# circuit1_ver1.net
KiCad netlist of a schematic drawn in Altium Designer
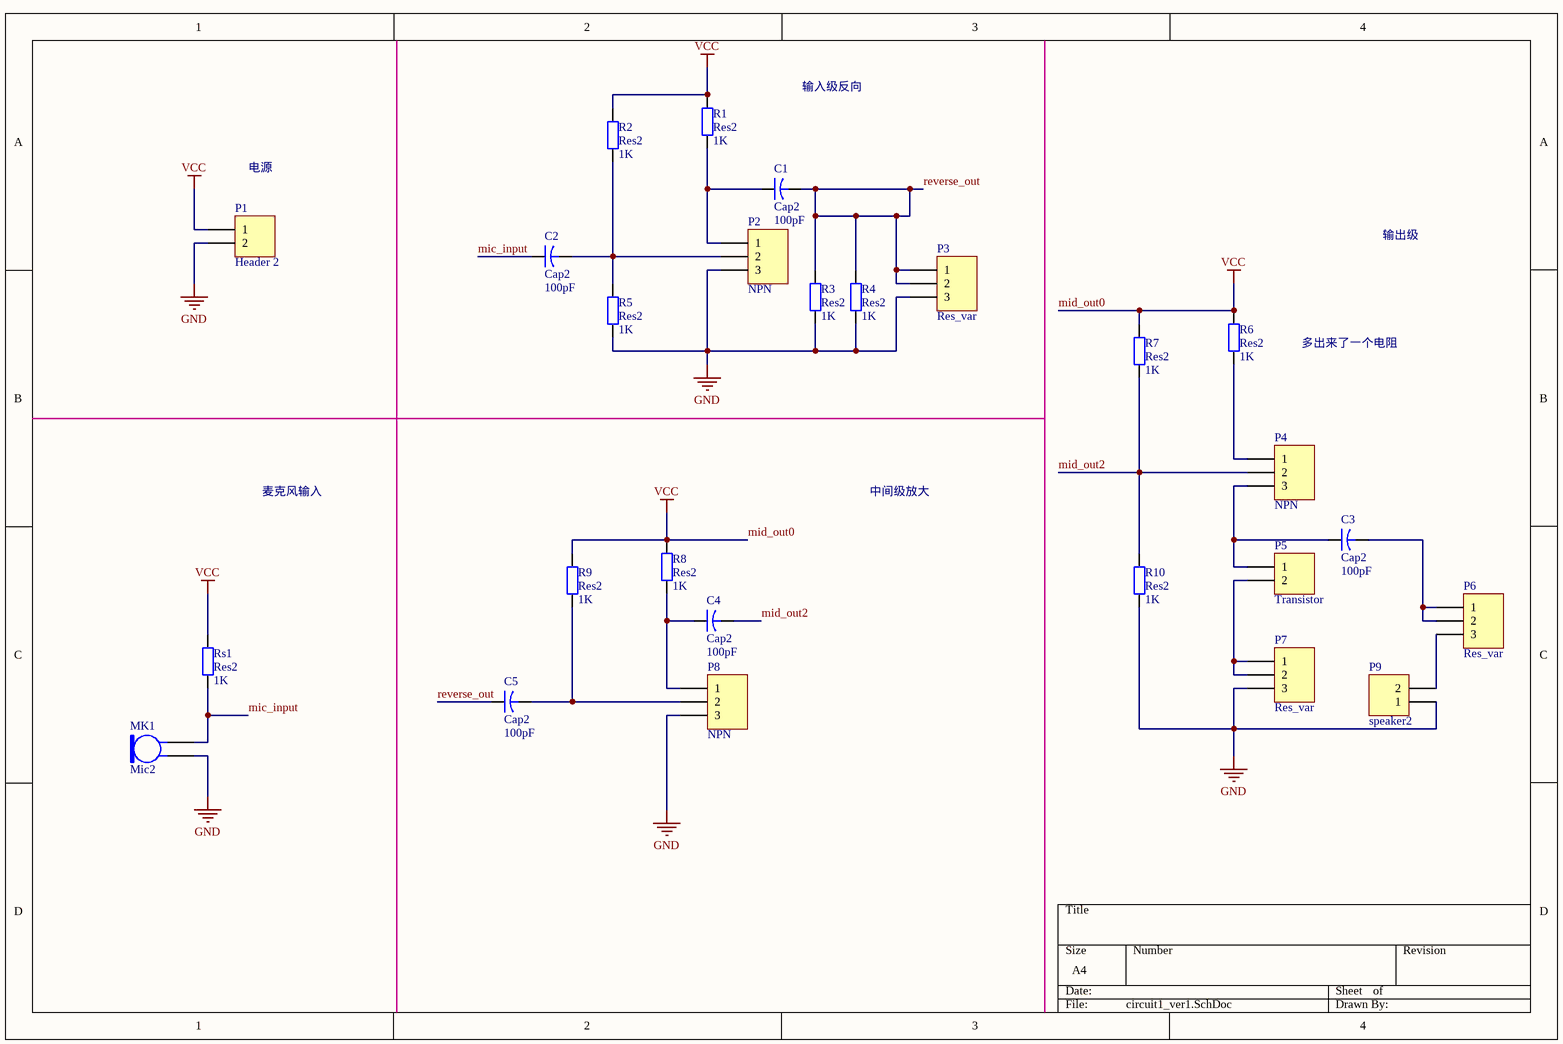
[diagram p0: circuit1_ver1.SchDoc]

(export (version "E")
  (design (tool "Eeschema 10.0.6"))
  (components
    (comp (ref "C1")
      (value "Cap2")
      (footprint "CAPR5-4X5")
      (description "Capacitor")
      (fields (field (name "ALTIUM_VALUE") "100pF") (field (name "PUBLISHER") "Altium Limited"))
      (libsource (lib "Miscellaneous Devices") (part "Cap2"))
    )
    (comp (ref "C2")
      (value "Cap2")
      (footprint "CAPR5-4X5")
      (description "Capacitor")
      (fields (field (name "ALTIUM_VALUE") "100pF") (field (name "PUBLISHER") "Altium Limited"))
      (libsource (lib "Miscellaneous Devices") (part "Cap2"))
    )
    (comp (ref "C3")
      (value "Cap2")
      (footprint "CAPR5-4X5")
      (description "Capacitor")
      (fields (field (name "ALTIUM_VALUE") "100pF") (field (name "PUBLISHER") "Altium Limited"))
      (libsource (lib "Miscellaneous Devices") (part "Cap2"))
    )
    (comp (ref "C4")
      (value "Cap2")
      (footprint "CAPR5-4X5")
      (description "Capacitor")
      (fields (field (name "ALTIUM_VALUE") "100pF") (field (name "PUBLISHER") "Altium Limited"))
      (libsource (lib "Miscellaneous Devices") (part "Cap2"))
    )
    (comp (ref "C5")
      (value "Cap2")
      (footprint "CAPR5-4X5")
      (description "Capacitor")
      (fields (field (name "ALTIUM_VALUE") "100pF") (field (name "PUBLISHER") "Altium Limited"))
      (libsource (lib "Miscellaneous Devices") (part "Cap2"))
    )
    (comp (ref "MK1")
      (value "Mic2")
      (footprint "PIN2")
      (description "Microphone")
      (fields (field (name "PUBLISHER") "Altium Limited"))
      (libsource (lib "Miscellaneous Devices") (part "Mic2"))
    )
    (comp (ref "P1")
      (value "Header 2")
      (footprint "HDR1X2")
      (description "Header, 2-Pin")
      (fields (field (name "PUBLISHER") "Altium Limited"))
      (libsource (lib "Miscellaneous Connectors") (part "Header 2"))
    )
    (comp (ref "P2")
      (value "NPN")
      (footprint "HDR1X3")
      (description "Header, 3-Pin")
      (fields (field (name "PUBLISHER") "Altium Limited"))
      (libsource (lib "Miscellaneous Connectors") (part "Header 3"))
    )
    (comp (ref "P3")
      (value "Res_var")
      (footprint "HDR1X3")
      (description "Header, 3-Pin")
      (fields (field (name "PUBLISHER") "Altium Limited"))
      (libsource (lib "Miscellaneous Connectors") (part "Header 3"))
    )
    (comp (ref "P4")
      (value "NPN")
      (footprint "HDR1X3")
      (description "Header, 3-Pin")
      (fields (field (name "PUBLISHER") "Altium Limited"))
      (libsource (lib "Miscellaneous Connectors") (part "Header 3"))
    )
    (comp (ref "P5")
      (value "Transistor")
      (footprint "HDR1X2")
      (description "Header, 2-Pin")
      (fields (field (name "PUBLISHER") "Altium Limited"))
      (libsource (lib "Miscellaneous Connectors") (part "Header 2"))
    )
    (comp (ref "P6")
      (value "Res_var")
      (footprint "HDR1X3")
      (description "Header, 3-Pin")
      (fields (field (name "PUBLISHER") "Altium Limited"))
      (libsource (lib "Miscellaneous Connectors") (part "Header 3"))
    )
    (comp (ref "P7")
      (value "Res_var")
      (footprint "HDR1X3")
      (description "Header, 3-Pin")
      (fields (field (name "PUBLISHER") "Altium Limited"))
      (libsource (lib "Miscellaneous Connectors") (part "Header 3"))
    )
    (comp (ref "P8")
      (value "NPN")
      (footprint "HDR1X3")
      (description "Header, 3-Pin")
      (fields (field (name "PUBLISHER") "Altium Limited"))
      (libsource (lib "Miscellaneous Connectors") (part "Header 3"))
    )
    (comp (ref "P9")
      (value "speaker2")
      (footprint "HDR1X2")
      (description "Header, 2-Pin")
      (fields (field (name "PUBLISHER") "Altium Limited"))
      (libsource (lib "") (part "Header 2_1"))
    )
    (comp (ref "R1")
      (value "Res2")
      (footprint "AXIAL-0.4")
      (description "Resistor")
      (fields (field (name "ALTIUM_VALUE") "1K") (field (name "PUBLISHER") "Altium Limited"))
      (libsource (lib "Miscellaneous Devices") (part "Res2"))
    )
    (comp (ref "R2")
      (value "Res2")
      (footprint "AXIAL-0.4")
      (description "Resistor")
      (fields (field (name "ALTIUM_VALUE") "1K") (field (name "PUBLISHER") "Altium Limited"))
      (libsource (lib "Miscellaneous Devices") (part "Res2"))
    )
    (comp (ref "R3")
      (value "Res2")
      (footprint "AXIAL-0.4")
      (description "Resistor")
      (fields (field (name "ALTIUM_VALUE") "1K") (field (name "PUBLISHER") "Altium Limited"))
      (libsource (lib "Miscellaneous Devices") (part "Res2"))
    )
    (comp (ref "R4")
      (value "Res2")
      (footprint "AXIAL-0.4")
      (description "Resistor")
      (fields (field (name "ALTIUM_VALUE") "1K") (field (name "PUBLISHER") "Altium Limited"))
      (libsource (lib "Miscellaneous Devices") (part "Res2"))
    )
    (comp (ref "R5")
      (value "Res2")
      (footprint "AXIAL-0.4")
      (description "Resistor")
      (fields (field (name "ALTIUM_VALUE") "1K") (field (name "PUBLISHER") "Altium Limited"))
      (libsource (lib "Miscellaneous Devices") (part "Res2"))
    )
    (comp (ref "R6")
      (value "Res2")
      (footprint "AXIAL-0.4")
      (description "Resistor")
      (fields (field (name "ALTIUM_VALUE") "1K") (field (name "PUBLISHER") "Altium Limited"))
      (libsource (lib "Miscellaneous Devices") (part "Res2"))
    )
    (comp (ref "R7")
      (value "Res2")
      (footprint "AXIAL-0.4")
      (description "Resistor")
      (fields (field (name "ALTIUM_VALUE") "1K") (field (name "PUBLISHER") "Altium Limited"))
      (libsource (lib "Miscellaneous Devices") (part "Res2"))
    )
    (comp (ref "R8")
      (value "Res2")
      (footprint "AXIAL-0.4")
      (description "Resistor")
      (fields (field (name "ALTIUM_VALUE") "1K") (field (name "PUBLISHER") "Altium Limited"))
      (libsource (lib "Miscellaneous Devices") (part "Res2"))
    )
    (comp (ref "R9")
      (value "Res2")
      (footprint "AXIAL-0.4")
      (description "Resistor")
      (fields (field (name "ALTIUM_VALUE") "1K") (field (name "PUBLISHER") "Altium Limited"))
      (libsource (lib "Miscellaneous Devices") (part "Res2"))
    )
    (comp (ref "R10")
      (value "Res2")
      (footprint "AXIAL-0.4")
      (description "Resistor")
      (fields (field (name "ALTIUM_VALUE") "1K") (field (name "PUBLISHER") "Altium Limited"))
      (libsource (lib "Miscellaneous Devices") (part "Res2"))
    )
    (comp (ref "Rs1")
      (value "Res2")
      (footprint "AXIAL-0.4")
      (description "Resistor")
      (fields (field (name "ALTIUM_VALUE") "1K") (field (name "PUBLISHER") "Altium Limited"))
      (libsource (lib "Miscellaneous Devices") (part "Res2"))
    )
  )
  (nets
    (net (code "1") (name "/mic_input") (class "Default")
      (node (ref "C2") (pin "1") (pinfunction "1_1") (pintype "passive"))
      (node (ref "MK1") (pin "2") (pinfunction "2_2") (pintype "passive"))
      (node (ref "Rs1") (pin "1") (pinfunction "1_1") (pintype "passive"))
    )
    (net (code "2") (name "/mid_out2") (class "Default")
      (node (ref "C4") (pin "2") (pinfunction "2_2") (pintype "passive"))
      (node (ref "P4") (pin "2") (pinfunction "2_2") (pintype "passive"))
      (node (ref "R10") (pin "2") (pinfunction "2_2") (pintype "passive"))
      (node (ref "R7") (pin "1") (pinfunction "1_1") (pintype "passive"))
    )
    (net (code "3") (name "/reverse_out") (class "Default")
      (node (ref "C1") (pin "2") (pinfunction "2_2") (pintype "passive"))
      (node (ref "C5") (pin "1") (pinfunction "1_1") (pintype "passive"))
      (node (ref "P3") (pin "1") (pinfunction "1_1") (pintype "passive"))
      (node (ref "P3") (pin "2") (pinfunction "2_2") (pintype "passive"))
      (node (ref "R3") (pin "2") (pinfunction "2_2") (pintype "passive"))
      (node (ref "R4") (pin "2") (pinfunction "2_2") (pintype "passive"))
    )
    (net (code "4") (name "GND") (class "Default")
      (node (ref "MK1") (pin "1") (pinfunction "1_1") (pintype "passive"))
      (node (ref "P1") (pin "2") (pinfunction "2_2") (pintype "passive"))
      (node (ref "P2") (pin "3") (pinfunction "3_3") (pintype "passive"))
      (node (ref "P3") (pin "3") (pinfunction "3_3") (pintype "passive"))
      (node (ref "P7") (pin "3") (pinfunction "3_3") (pintype "passive"))
      (node (ref "P8") (pin "3") (pinfunction "3_3") (pintype "passive"))
      (node (ref "P9") (pin "1") (pinfunction "1_1") (pintype "passive"))
      (node (ref "R10") (pin "1") (pinfunction "1_1") (pintype "passive"))
      (node (ref "R3") (pin "1") (pinfunction "1_1") (pintype "passive"))
      (node (ref "R4") (pin "1") (pinfunction "1_1") (pintype "passive"))
      (node (ref "R5") (pin "1") (pinfunction "1_1") (pintype "passive"))
    )
    (net (code "5") (name "Net-(C1-Pad1)") (class "Default")
      (node (ref "C1") (pin "1") (pinfunction "1_1") (pintype "passive"))
      (node (ref "P2") (pin "1") (pinfunction "1_1") (pintype "passive"))
      (node (ref "R1") (pin "1") (pinfunction "1_1") (pintype "passive"))
    )
    (net (code "6") (name "Net-(C2-Pad2)") (class "Default")
      (node (ref "C2") (pin "2") (pinfunction "2_2") (pintype "passive"))
      (node (ref "P2") (pin "2") (pinfunction "2_2") (pintype "passive"))
      (node (ref "R2") (pin "1") (pinfunction "1_1") (pintype "passive"))
      (node (ref "R5") (pin "2") (pinfunction "2_2") (pintype "passive"))
    )
    (net (code "7") (name "Net-(C3-Pad1)") (class "Default")
      (node (ref "C3") (pin "1") (pinfunction "1_1") (pintype "passive"))
      (node (ref "P4") (pin "3") (pinfunction "3_3") (pintype "passive"))
      (node (ref "P5") (pin "1") (pinfunction "1_1") (pintype "passive"))
    )
    (net (code "8") (name "Net-(C3-Pad2)") (class "Default")
      (node (ref "C3") (pin "2") (pinfunction "2_2") (pintype "passive"))
      (node (ref "P6") (pin "1") (pinfunction "1_1") (pintype "passive"))
      (node (ref "P6") (pin "2") (pinfunction "2_2") (pintype "passive"))
    )
    (net (code "9") (name "Net-(C4-Pad1)") (class "Default")
      (node (ref "C4") (pin "1") (pinfunction "1_1") (pintype "passive"))
      (node (ref "P8") (pin "1") (pinfunction "1_1") (pintype "passive"))
      (node (ref "R8") (pin "1") (pinfunction "1_1") (pintype "passive"))
    )
    (net (code "10") (name "Net-(C5-Pad2)") (class "Default")
      (node (ref "C5") (pin "2") (pinfunction "2_2") (pintype "passive"))
      (node (ref "P8") (pin "2") (pinfunction "2_2") (pintype "passive"))
      (node (ref "R9") (pin "1") (pinfunction "1_1") (pintype "passive"))
    )
    (net (code "11") (name "Net-(P4-Pad1)") (class "Default")
      (node (ref "P4") (pin "1") (pinfunction "1_1") (pintype "passive"))
      (node (ref "R6") (pin "1") (pinfunction "1_1") (pintype "passive"))
    )
    (net (code "12") (name "Net-(P5-Pad2)") (class "Default")
      (node (ref "P5") (pin "2") (pinfunction "2_2") (pintype "passive"))
      (node (ref "P7") (pin "1") (pinfunction "1_1") (pintype "passive"))
      (node (ref "P7") (pin "2") (pinfunction "2_2") (pintype "passive"))
    )
    (net (code "13") (name "Net-(P6-Pad3)") (class "Default")
      (node (ref "P6") (pin "3") (pinfunction "3_3") (pintype "passive"))
      (node (ref "P9") (pin "2") (pinfunction "2_2") (pintype "passive"))
    )
    (net (code "14") (name "VCC") (class "Default")
      (node (ref "P1") (pin "1") (pinfunction "1_1") (pintype "passive"))
      (node (ref "R1") (pin "2") (pinfunction "2_2") (pintype "passive"))
      (node (ref "R2") (pin "2") (pinfunction "2_2") (pintype "passive"))
      (node (ref "R6") (pin "2") (pinfunction "2_2") (pintype "passive"))
      (node (ref "R7") (pin "2") (pinfunction "2_2") (pintype "passive"))
      (node (ref "R8") (pin "2") (pinfunction "2_2") (pintype "passive"))
      (node (ref "R9") (pin "2") (pinfunction "2_2") (pintype "passive"))
      (node (ref "Rs1") (pin "2") (pinfunction "2_2") (pintype "passive"))
    )
  )
)
